# Quark.net
KiCad netlist of a schematic drawn in EasyEDA Pro
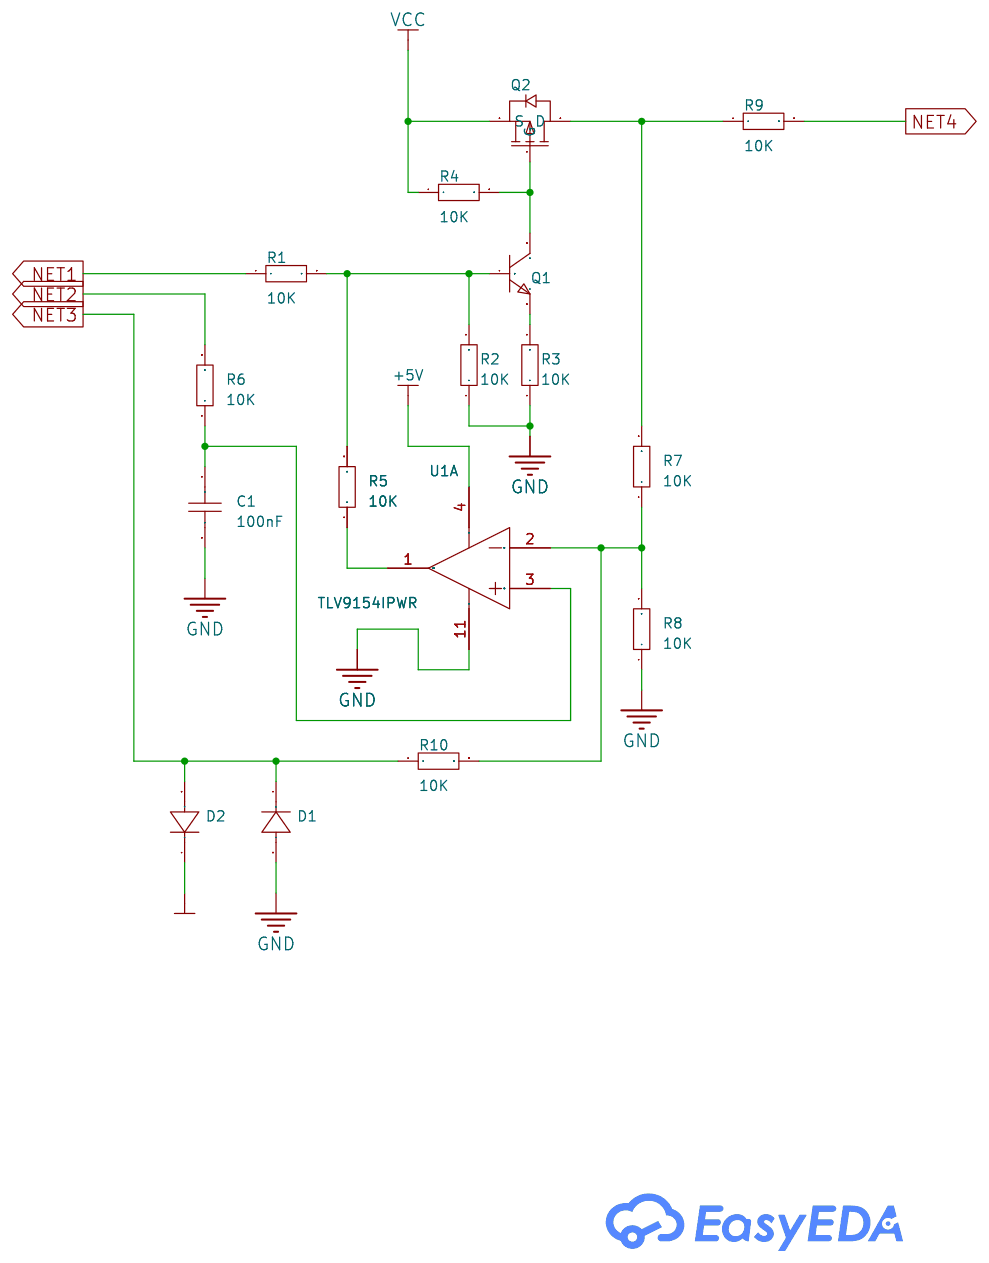
[diagram p0: schematic sheet]

(export (version "E")
  (design (tool "Eeschema 10.0.6"))
  (components
    (comp (ref "C1")
      (value "100nF")
      (footprint "easyedapro:C0201")
      (libsource (lib "easyedapro") (part "CAP"))
    )
    (comp (ref "D1")
      (value "~")
      (footprint "easyedapro:DO-41_BD2.4-L4.7-P8.70-D0.9-RD")
      (libsource (lib "easyedapro") (part "D_1N4007"))
    )
    (comp (ref "D2")
      (value "~")
      (footprint "easyedapro:DO-41_BD2.4-L4.7-P8.70-D0.9-RD")
      (libsource (lib "easyedapro") (part "D_1N4007"))
    )
    (comp (ref "Q1")
      (value "~")
      (footprint "easyedapro:SOT-23_L2.9-W1.3-P1.90-LS2.4-BR")
      (libsource (lib "easyedapro") (part "NPN"))
    )
    (comp (ref "Q2")
      (value "~")
      (footprint "easyedapro:SOT-23_L2.9-W1.3-P1.90-LS2.4-BR")
      (libsource (lib "easyedapro") (part "P_MOS"))
    )
    (comp (ref "R1") (value "10K") (footprint "easyedapro:R0603") (libsource (lib "easyedapro") (part "Res")))
    (comp (ref "R2") (value "10K") (footprint "easyedapro:R0603") (libsource (lib "easyedapro") (part "Res")))
    (comp (ref "R3") (value "10K") (footprint "easyedapro:R0603") (libsource (lib "easyedapro") (part "Res")))
    (comp (ref "R4") (value "10K") (footprint "easyedapro:R0603") (libsource (lib "easyedapro") (part "Res")))
    (comp (ref "R5") (value "10K") (footprint "easyedapro:R0603") (libsource (lib "easyedapro") (part "Res")))
    (comp (ref "R6") (value "10K") (footprint "easyedapro:R0603") (libsource (lib "easyedapro") (part "Res")))
    (comp (ref "R7") (value "10K") (footprint "easyedapro:R0603") (libsource (lib "easyedapro") (part "Res")))
    (comp (ref "R8") (value "10K") (footprint "easyedapro:R0603") (libsource (lib "easyedapro") (part "Res")))
    (comp (ref "R9") (value "10K") (footprint "easyedapro:R0603") (libsource (lib "easyedapro") (part "Res")))
    (comp (ref "R10")
      (value "10K")
      (footprint "easyedapro:R0603")
      (libsource (lib "easyedapro") (part "Res"))
    )
    (comp (ref "U1")
      (value "TLV9154IPWR")
      (footprint "easyedapro:TSSOP-14_L5.0-W4.4-P0.65-LS6.4-BL")
      (fields (field (name "Manufacturer") "TI(德州仪器)"))
      (libsource (lib "easyedapro") (part "TLV9154IPWR"))
    )
  )
  (nets
    (net (code "1") (name "+3.3") (class "Default")
      (node (ref "D2") (pin "1") (pinfunction "K_1") (pintype "input"))
    )
    (net (code "2") (name "+5V") (class "Default")
      (node (ref "U1") (pin "4") (pinfunction "V+_4") (pintype "unspecified"))
    )
    (net (code "3") (name "GND") (class "Default")
      (node (ref "C1") (pin "2") (pinfunction "2_2") (pintype "input"))
      (node (ref "D1") (pin "2") (pinfunction "A_2") (pintype "input"))
      (node (ref "R2") (pin "1") (pinfunction "1_1") (pintype "input"))
      (node (ref "R3") (pin "1") (pinfunction "1_1") (pintype "input"))
      (node (ref "R8") (pin "1") (pinfunction "1_1") (pintype "input"))
      (node (ref "U1") (pin "11") (pinfunction "V-_11") (pintype "unspecified"))
    )
    (net (code "4") (name "NET1") (class "Default")
      (node (ref "R1") (pin "1") (pinfunction "1_1") (pintype "input"))
    )
    (net (code "5") (name "NET2") (class "Default")
      (node (ref "R6") (pin "2") (pinfunction "2_2") (pintype "input"))
    )
    (net (code "6") (name "NET3") (class "Default")
      (node (ref "D1") (pin "1") (pinfunction "K_1") (pintype "input"))
      (node (ref "D2") (pin "2") (pinfunction "A_2") (pintype "input"))
      (node (ref "R10") (pin "1") (pinfunction "1_1") (pintype "input"))
    )
    (net (code "7") (name "NET4") (class "Default")
      (node (ref "R9") (pin "2") (pinfunction "2_2") (pintype "input"))
    )
    (net (code "8") (name "Net-(Q1-B)") (class "Default")
      (node (ref "Q1") (pin "1") (pinfunction "B_1") (pintype "unspecified"))
      (node (ref "R1") (pin "2") (pinfunction "2_2") (pintype "input"))
      (node (ref "R2") (pin "2") (pinfunction "2_2") (pintype "input"))
      (node (ref "R5") (pin "2") (pinfunction "2_2") (pintype "input"))
    )
    (net (code "9") (name "Net-(Q1-C)") (class "Default")
      (node (ref "Q1") (pin "3") (pinfunction "C_3") (pintype "unspecified"))
      (node (ref "Q2") (pin "1") (pinfunction "G_1") (pintype "input"))
      (node (ref "R4") (pin "2") (pinfunction "2_2") (pintype "input"))
    )
    (net (code "10") (name "Net-(Q1-E)") (class "Default")
      (node (ref "Q1") (pin "2") (pinfunction "E_2") (pintype "unspecified"))
      (node (ref "R3") (pin "2") (pinfunction "2_2") (pintype "input"))
    )
    (net (code "11") (name "Net-(Q2-D)") (class "Default")
      (node (ref "Q2") (pin "3") (pinfunction "D_3") (pintype "input"))
      (node (ref "R7") (pin "2") (pinfunction "2_2") (pintype "input"))
      (node (ref "R9") (pin "1") (pinfunction "1_1") (pintype "input"))
    )
    (net (code "12") (name "Net-(U1A-IN1+)") (class "Default")
      (node (ref "C1") (pin "1") (pinfunction "1_1") (pintype "input"))
      (node (ref "R6") (pin "1") (pinfunction "1_1") (pintype "input"))
      (node (ref "U1") (pin "3") (pinfunction "IN1+_3") (pintype "unspecified"))
    )
    (net (code "13") (name "Net-(U1A-IN1-)") (class "Default")
      (node (ref "R10") (pin "2") (pinfunction "2_2") (pintype "input"))
      (node (ref "R7") (pin "1") (pinfunction "1_1") (pintype "input"))
      (node (ref "R8") (pin "2") (pinfunction "2_2") (pintype "input"))
      (node (ref "U1") (pin "2") (pinfunction "IN1-_2") (pintype "unspecified"))
    )
    (net (code "14") (name "Net-(U1A-OUT1)") (class "Default")
      (node (ref "R5") (pin "1") (pinfunction "1_1") (pintype "input"))
      (node (ref "U1") (pin "1") (pinfunction "OUT1_1") (pintype "output"))
    )
    (net (code "15") (name "VCC") (class "Default")
      (node (ref "Q2") (pin "2") (pinfunction "S_2") (pintype "input"))
      (node (ref "R4") (pin "1") (pinfunction "1_1") (pintype "input"))
    )
  )
)
